# Processor.net
KiCad netlist of a schematic drawn in Altium Designer
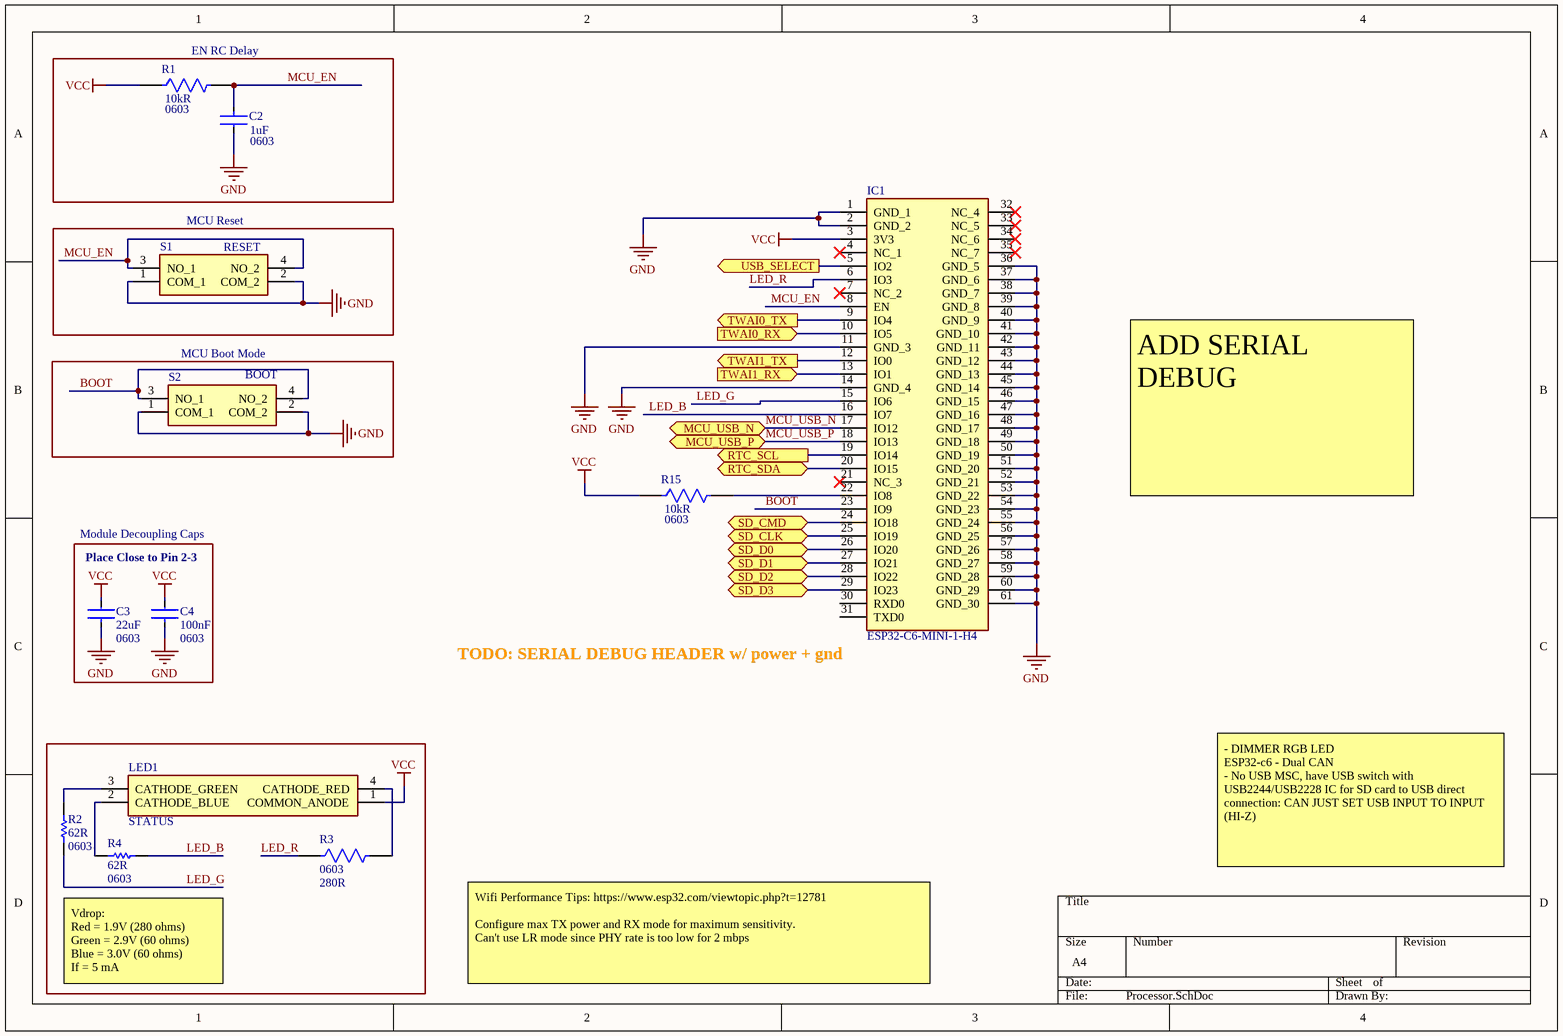
[diagram p0: Processor.SchDoc]

(export (version "E")
  (design (tool "Eeschema 10.0.6"))
  (components
    (comp (ref "C2")
      (value "UMK107BJ105KA-T")
      (footprint "FP-0603-L_1_6_0_1-W_0_8_0-IPC_A")
      (description "None")
      (fields
        (field (name "TOLERANCE") "10%")
        (field (name "CASE/PACKAGE") "0603")
        (field (name "CAPACITANCE") "1uF")
      )
      (libsource (lib "Altium Content Vault") (part "02cd4be3c70576c341d710602a673aa"))
    )
    (comp (ref "C3")
      (value "GRM188R61A226ME15D")
      (footprint "FP-GRM188-0_2-IPC_C")
      (description "Chip Multilayer Ceramic Capacitors for General Purpose, 0603, 22uF, X5R, 15%, 20%, 10V")
      (fields
        (field (name "TOLERANCE") "20%")
        (field (name "CAPACITANCE") "22uF")
        (field (name "CASE CODE (IMPERIAL)") "0603")
      )
      (libsource (lib "Altium Content Vault") (part "11868f565c42a9108669ba33697ecf6"))
    )
    (comp (ref "C4")
      (value "CL10B104KB8WPNC")
      (footprint "FP-CL10-IPC_A")
      (description "Cap Ceramic 100nF 50V X7R ±10% Pad SMD 0603 +125°C T/R")
      (fields
        (field (name "CAPACITANCE") "100nF")
        (field (name "CASE/PACKAGE") "0603")
        (field (name "TOLERANCE") "10%")
      )
      (libsource (lib "Altium Content Vault") (part "b4654b650e69147ec39a6b967a45e02"))
    )
    (comp (ref "IC1")
      (value "ESP32-C6-MINI-1-H4")
      (footprint "ESP32C6MINI1H4")
      (description "Integrated Circuit")
      (fields (field (name "MOUSER PART NUMBER") "356-ESP32C6MINI1-H4"))
      (libsource (lib "WiCAN_lib") (part "ESP32-C6-MINI-1-H4"))
    )
    (comp (ref "LED1")
      (value "STATUS")
      (footprint "CLMVCFKACL1D1L71BB7C3C3")
      (description "LED")
      (fields
        (field (name "MANUFACTURER_PART_NUMBER") "CLMVC-FKA-CL1D1L71BB7C3C3")
        (field (name "MOUSER PART NUMBER") "941-CLMVCFKACL1D1L71")
      )
      (libsource (lib "WiCAN_lib") (part "CLMVC-FKA-CL1D1L71BB7C3C3"))
    )
    (comp (ref "R1")
      (value "RMCF0603JG10K0")
      (footprint "FP-RMCF0603-MFG")
      (description "10kΩ ±5% 0.1W 0603 Thick Film Chip Resistor AEC-Q200 compliant")
      (fields
        (field (name "TOLERANCE") "5%")
        (field (name "CASE CODE (IMPERIAL)") "0603")
        (field (name "RESISTANCE") "10kR")
      )
      (libsource (lib "Altium Content Vault") (part "1029c3af85768c4190bb7ad29bc67b5"))
    )
    (comp (ref "R2")
      (value "ERJ-3GEYJ620V")
      (footprint "RESC1608X55X30ML15T15")
      (fields
        (field (name "MANUFACTURER") "Panasonic")
        (field (name "RESISTANCE") "62R")
        (field (name "PACKAGE") "0603")
      )
      (libsource (lib "Altium Content Vault") (part "RES"))
    )
    (comp (ref "R3")
      (value "RMCF0603FT280R")
      (footprint "FP-RMCF0603-MFG")
      (description "280Ω ±1% 0.1W 0603 Thick Film Chip Resistor AEC-Q200 compliant")
      (fields
        (field (name "CASE/PACKAGE") "0603")
        (field (name "TOLERANCE") "1%")
        (field (name "RESISTANCE") "280R")
      )
      (libsource (lib "Altium Content Vault") (part "1029c3af85768c4190bb7ad29bc67b5"))
    )
    (comp (ref "R4")
      (value "ERJ-3GEYJ620V")
      (footprint "RESC1608X55X30ML15T15")
      (fields
        (field (name "MANUFACTURER") "Panasonic")
        (field (name "RESISTANCE") "62R")
        (field (name "PACKAGE") "0603")
      )
      (libsource (lib "Altium Content Vault") (part "RES"))
    )
    (comp (ref "R15")
      (value "RMCF0603JG10K0")
      (footprint "FP-RMCF0603-MFG")
      (description "10kΩ ±5% 0.1W 0603 Thick Film Chip Resistor AEC-Q200 compliant")
      (fields
        (field (name "TOLERANCE") "5%")
        (field (name "CASE CODE (IMPERIAL)") "0603")
        (field (name "RESISTANCE") "10kR")
      )
      (libsource (lib "Altium Content Vault") (part "1029c3af85768c4190bb7ad29bc67b5"))
    )
    (comp (ref "S1")
      (value "RESET")
      (footprint "PTS526SM15SMTR2LFS")
      (description "Switch")
      (fields
        (field (name "MANUFACTURER_PART_NUMBER") "PTS526 SM15 SMTR2 LFS")
        (field (name "MOUSER PART NUMBER") "611-PTS526SM15SMTR2L")
      )
      (libsource (lib "WiCAN_lib") (part "PTS526_SM15_SMTR2_LFS"))
    )
    (comp (ref "S2")
      (value "BOOT")
      (footprint "PTS526SM15SMTR2LFS")
      (description "Switch")
      (fields
        (field (name "MANUFACTURER_PART_NUMBER") "PTS526 SM15 SMTR2 LFS")
        (field (name "MOUSER PART NUMBER") "611-PTS526SM15SMTR2L")
      )
      (libsource (lib "WiCAN_lib") (part "PTS526_SM15_SMTR2_LFS"))
    )
  )
  (nets
    (net (code "1") (name "/BOOT") (class "Default")
      (node (ref "IC1") (pin "23") (pinfunction "IO9_23") (pintype "passive"))
      (node (ref "S2") (pin "3") (pinfunction "NO_1_3") (pintype "passive"))
      (node (ref "S2") (pin "4") (pinfunction "NO_2_4") (pintype "passive"))
    )
    (net (code "2") (name "/LED_B") (class "Default")
      (node (ref "IC1") (pin "16") (pinfunction "IO7_16") (pintype "passive"))
      (node (ref "R4") (pin "2") (pinfunction "2_2") (pintype "passive"))
    )
    (net (code "3") (name "/LED_G") (class "Default")
      (node (ref "IC1") (pin "15") (pinfunction "IO6_15") (pintype "passive"))
      (node (ref "R2") (pin "2") (pinfunction "2_2") (pintype "passive"))
    )
    (net (code "4") (name "/LED_R") (class "Default")
      (node (ref "IC1") (pin "6") (pinfunction "IO3_6") (pintype "passive"))
      (node (ref "R3") (pin "1") (pinfunction "1_1") (pintype "passive"))
    )
    (net (code "5") (name "/MCU_EN") (class "Default")
      (node (ref "C2") (pin "1") (pinfunction "1_1") (pintype "passive"))
      (node (ref "IC1") (pin "8") (pinfunction "EN_8") (pintype "passive"))
      (node (ref "R1") (pin "2") (pinfunction "2_2") (pintype "passive"))
      (node (ref "S1") (pin "3") (pinfunction "NO_1_3") (pintype "passive"))
      (node (ref "S1") (pin "4") (pinfunction "NO_2_4") (pintype "passive"))
    )
    (net (code "6") (name "/MCU_USB_N") (class "Default")
      (node (ref "IC1") (pin "17") (pinfunction "IO12_17") (pintype "passive"))
    )
    (net (code "7") (name "/MCU_USB_P") (class "Default")
      (node (ref "IC1") (pin "18") (pinfunction "IO13_18") (pintype "passive"))
    )
    (net (code "8") (name "/RTC_SCL") (class "Default")
      (node (ref "IC1") (pin "19") (pinfunction "IO14_19") (pintype "passive"))
    )
    (net (code "9") (name "/RTC_SDA") (class "Default")
      (node (ref "IC1") (pin "20") (pinfunction "IO15_20") (pintype "passive"))
    )
    (net (code "10") (name "/SD_CLK") (class "Default")
      (node (ref "IC1") (pin "25") (pinfunction "IO19_25") (pintype "passive"))
    )
    (net (code "11") (name "/SD_CMD") (class "Default")
      (node (ref "IC1") (pin "24") (pinfunction "IO18_24") (pintype "passive"))
    )
    (net (code "12") (name "/SD_D0") (class "Default")
      (node (ref "IC1") (pin "26") (pinfunction "IO20_26") (pintype "passive"))
    )
    (net (code "13") (name "/SD_D1") (class "Default")
      (node (ref "IC1") (pin "27") (pinfunction "IO21_27") (pintype "passive"))
    )
    (net (code "14") (name "/SD_D2") (class "Default")
      (node (ref "IC1") (pin "28") (pinfunction "IO22_28") (pintype "passive"))
    )
    (net (code "15") (name "/SD_D3") (class "Default")
      (node (ref "IC1") (pin "29") (pinfunction "IO23_29") (pintype "passive"))
    )
    (net (code "16") (name "/TWAI0_RX") (class "Default")
      (node (ref "IC1") (pin "10") (pinfunction "IO5_10") (pintype "passive"))
    )
    (net (code "17") (name "/TWAI0_TX") (class "Default")
      (node (ref "IC1") (pin "9") (pinfunction "IO4_9") (pintype "passive"))
    )
    (net (code "18") (name "/TWAI1_RX") (class "Default")
      (node (ref "IC1") (pin "13") (pinfunction "IO1_13") (pintype "passive"))
    )
    (net (code "19") (name "/TWAI1_TX") (class "Default")
      (node (ref "IC1") (pin "12") (pinfunction "IO0_12") (pintype "passive"))
    )
    (net (code "20") (name "/USB_SELECT") (class "Default")
      (node (ref "IC1") (pin "5") (pinfunction "IO2_5") (pintype "passive"))
    )
    (net (code "21") (name "GND") (class "Default")
      (node (ref "C2") (pin "2") (pinfunction "2_2") (pintype "passive"))
      (node (ref "C3") (pin "1") (pinfunction "1_1") (pintype "passive"))
      (node (ref "C4") (pin "1") (pinfunction "1_1") (pintype "passive"))
      (node (ref "IC1") (pin "1") (pinfunction "GND_1_1") (pintype "passive"))
      (node (ref "IC1") (pin "11") (pinfunction "GND_3_11") (pintype "passive"))
      (node (ref "IC1") (pin "14") (pinfunction "GND_4_14") (pintype "passive"))
      (node (ref "IC1") (pin "2") (pinfunction "GND_2_2") (pintype "passive"))
      (node (ref "IC1") (pin "36") (pinfunction "GND_5_36") (pintype "passive"))
      (node (ref "IC1") (pin "37") (pinfunction "GND_6_37") (pintype "passive"))
      (node (ref "IC1") (pin "38") (pinfunction "GND_7_38") (pintype "passive"))
      (node (ref "IC1") (pin "39") (pinfunction "GND_8_39") (pintype "passive"))
      (node (ref "IC1") (pin "40") (pinfunction "GND_9_40") (pintype "passive"))
      (node (ref "IC1") (pin "41") (pinfunction "GND_10_41") (pintype "passive"))
      (node (ref "IC1") (pin "42") (pinfunction "GND_11_42") (pintype "passive"))
      (node (ref "IC1") (pin "43") (pinfunction "GND_12_43") (pintype "passive"))
      (node (ref "IC1") (pin "44") (pinfunction "GND_13_44") (pintype "passive"))
      (node (ref "IC1") (pin "45") (pinfunction "GND_14_45") (pintype "passive"))
      (node (ref "IC1") (pin "46") (pinfunction "GND_15_46") (pintype "passive"))
      (node (ref "IC1") (pin "47") (pinfunction "GND_16_47") (pintype "passive"))
      (node (ref "IC1") (pin "48") (pinfunction "GND_17_48") (pintype "passive"))
      (node (ref "IC1") (pin "49") (pinfunction "GND_18_49") (pintype "passive"))
      (node (ref "IC1") (pin "50") (pinfunction "GND_19_50") (pintype "passive"))
      (node (ref "IC1") (pin "51") (pinfunction "GND_20_51") (pintype "passive"))
      (node (ref "IC1") (pin "52") (pinfunction "GND_21_52") (pintype "passive"))
      (node (ref "IC1") (pin "53") (pinfunction "GND_22_53") (pintype "passive"))
      (node (ref "IC1") (pin "54") (pinfunction "GND_23_54") (pintype "passive"))
      (node (ref "IC1") (pin "55") (pinfunction "GND_24_55") (pintype "passive"))
      (node (ref "IC1") (pin "56") (pinfunction "GND_25_56") (pintype "passive"))
      (node (ref "IC1") (pin "57") (pinfunction "GND_26_57") (pintype "passive"))
      (node (ref "IC1") (pin "58") (pinfunction "GND_27_58") (pintype "passive"))
      (node (ref "IC1") (pin "59") (pinfunction "GND_28_59") (pintype "passive"))
      (node (ref "IC1") (pin "60") (pinfunction "GND_29_60") (pintype "passive"))
      (node (ref "IC1") (pin "61") (pinfunction "GND_30_61") (pintype "passive"))
      (node (ref "S1") (pin "1") (pinfunction "COM_1_1") (pintype "passive"))
      (node (ref "S1") (pin "2") (pinfunction "COM_2_2") (pintype "passive"))
      (node (ref "S2") (pin "1") (pinfunction "COM_1_1") (pintype "passive"))
      (node (ref "S2") (pin "2") (pinfunction "COM_2_2") (pintype "passive"))
    )
    (net (code "22") (name "Net-(IC1-IO8)") (class "Default")
      (node (ref "IC1") (pin "22") (pinfunction "IO8_22") (pintype "passive"))
      (node (ref "R15") (pin "2") (pinfunction "2_2") (pintype "passive"))
    )
    (net (code "23") (name "Net-(LED1-CATHODE_BLUE)") (class "Default")
      (node (ref "LED1") (pin "2") (pinfunction "CATHODE_BLUE_2") (pintype "passive"))
      (node (ref "R4") (pin "1") (pinfunction "1_1") (pintype "passive"))
    )
    (net (code "24") (name "Net-(LED1-CATHODE_GREEN)") (class "Default")
      (node (ref "LED1") (pin "3") (pinfunction "CATHODE_GREEN_3") (pintype "passive"))
      (node (ref "R2") (pin "1") (pinfunction "1_1") (pintype "passive"))
    )
    (net (code "25") (name "Net-(LED1-CATHODE_RED)") (class "Default")
      (node (ref "LED1") (pin "4") (pinfunction "CATHODE_RED_4") (pintype "passive"))
      (node (ref "R3") (pin "2") (pinfunction "2_2") (pintype "passive"))
    )
    (net (code "26") (name "VCC") (class "Default")
      (node (ref "C3") (pin "2") (pinfunction "2_2") (pintype "passive"))
      (node (ref "C4") (pin "2") (pinfunction "2_2") (pintype "passive"))
      (node (ref "IC1") (pin "3") (pinfunction "3V3_3") (pintype "passive"))
      (node (ref "LED1") (pin "1") (pinfunction "COMMON_ANODE_1") (pintype "passive"))
      (node (ref "R1") (pin "1") (pinfunction "1_1") (pintype "passive"))
      (node (ref "R15") (pin "1") (pinfunction "1_1") (pintype "passive"))
    )
    (net (code "27") (name "unconnected-(IC1-NC_1-Pad4)") (class "Default")
      (node (ref "IC1") (pin "4") (pinfunction "NC_1_4") (pintype "passive+no_connect"))
    )
    (net (code "28") (name "unconnected-(IC1-NC_2-Pad7)") (class "Default")
      (node (ref "IC1") (pin "7") (pinfunction "NC_2_7") (pintype "passive+no_connect"))
    )
    (net (code "29") (name "unconnected-(IC1-NC_3-Pad21)") (class "Default")
      (node (ref "IC1") (pin "21") (pinfunction "NC_3_21") (pintype "passive+no_connect"))
    )
    (net (code "30") (name "unconnected-(IC1-NC_4-Pad32)") (class "Default")
      (node (ref "IC1") (pin "32") (pinfunction "NC_4_32") (pintype "passive+no_connect"))
    )
    (net (code "31") (name "unconnected-(IC1-NC_5-Pad33)") (class "Default")
      (node (ref "IC1") (pin "33") (pinfunction "NC_5_33") (pintype "passive+no_connect"))
    )
    (net (code "32") (name "unconnected-(IC1-NC_6-Pad34)") (class "Default")
      (node (ref "IC1") (pin "34") (pinfunction "NC_6_34") (pintype "passive+no_connect"))
    )
    (net (code "33") (name "unconnected-(IC1-NC_7-Pad35)") (class "Default")
      (node (ref "IC1") (pin "35") (pinfunction "NC_7_35") (pintype "passive+no_connect"))
    )
    (net (code "34") (name "unconnected-(IC1-RXD0-Pad30)") (class "Default")
      (node (ref "IC1") (pin "30") (pinfunction "RXD0_30") (pintype "passive"))
    )
    (net (code "35") (name "unconnected-(IC1-TXD0-Pad31)") (class "Default")
      (node (ref "IC1") (pin "31") (pinfunction "TXD0_31") (pintype "passive"))
    )
  )
)
